# hv_Isolation.net
KiCad netlist of a schematic drawn in Altium Designer
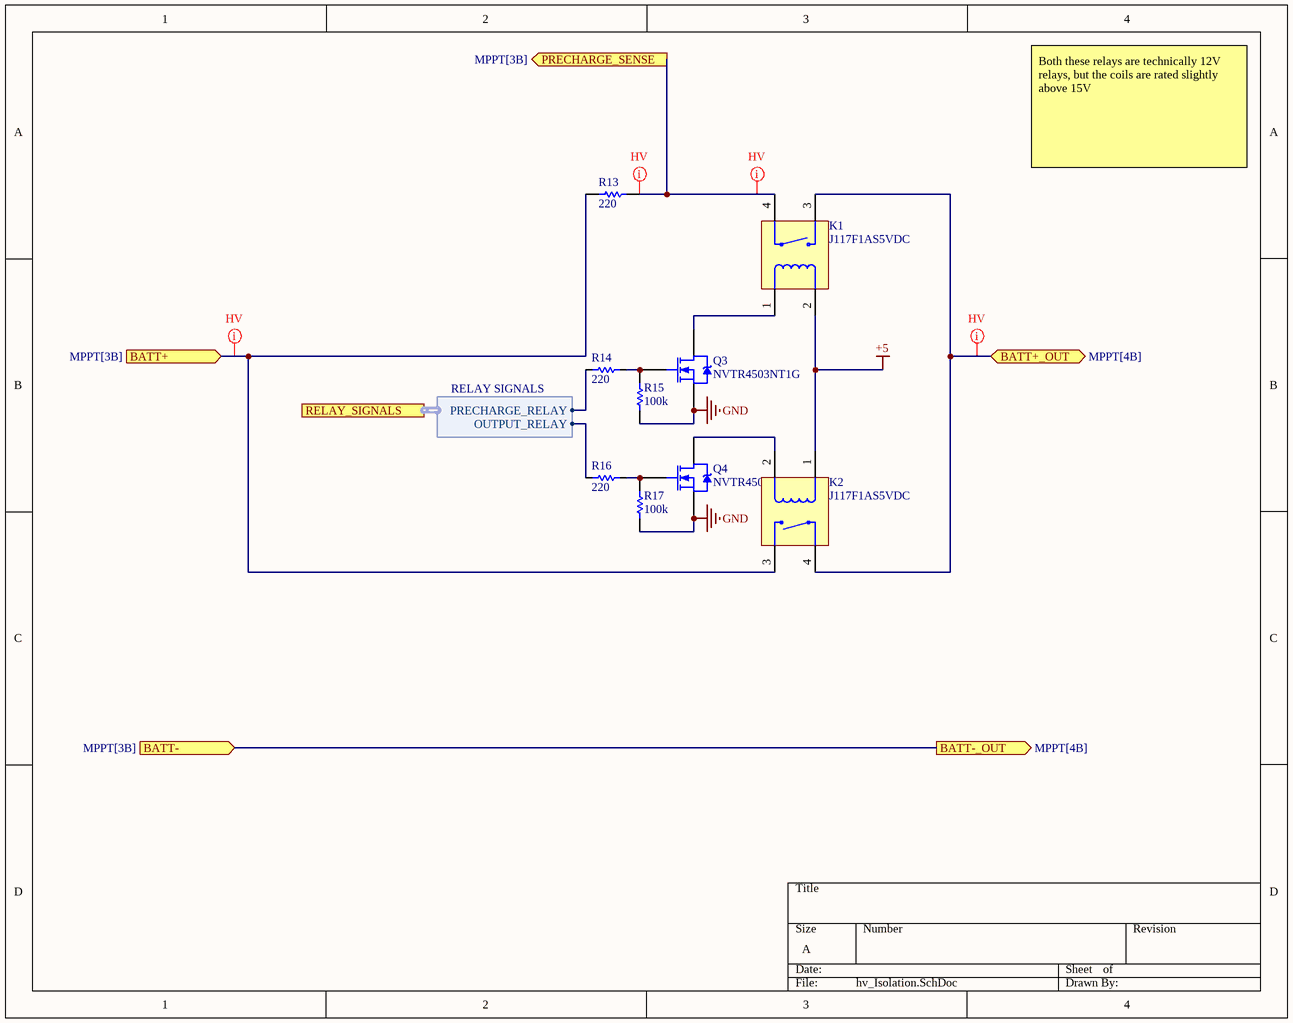
[diagram p0: hv_Isolation.SchDoc]

(export (version "E")
  (design (tool "Eeschema 10.0.6"))
  (components
    (comp (ref "K1")
      (value "J117F1AS5VDC")
      (footprint "J117F1AS5VDC-Footprint")
      (description "Relay Gen Purpose SPST 10A 5V")
      (libsource (lib "University of Minnesota - Solar Vehicle Project") (part "Symbol"))
    )
    (comp (ref "K2")
      (value "J117F1AS5VDC")
      (footprint "J117F1AS5VDC-Footprint")
      (description "Relay Gen Purpose SPST 10A 5V")
      (libsource (lib "") (part "Symbol_2"))
    )
    (comp (ref "Q3")
      (value "NVTR4503NT1G")
      (footprint "SOT-23_N")
      (libsource (lib "University of Minnesota - Solar Vehicle Project") (part "Q_MOSFET N-CH 30V 5A"))
    )
    (comp (ref "Q4")
      (value "NVTR4503NT1G")
      (footprint "SOT-23_N")
      (libsource (lib "University of Minnesota - Solar Vehicle Project") (part "Q_MOSFET N-CH 30V 5A"))
    )
    (comp (ref "R13")
      (value "220")
      (footprint "R_Res_Axial_SQP_THRU")
      (description "Fixed Resistor, Wire Wound, 10W, 220ohm, 750V, 5% +/-Tol, 300ppm/Cel, Through Hole Mount")
      (fields (field (name "TOLERANCE") "5%") (field (name "POWER") "10W"))
      (libsource (lib "University of Minnesota - Solar Vehicle Project") (part "RES-2"))
    )
    (comp (ref "R14")
      (value "220")
      (footprint "0603_RESISTOR")
      (description "RES 220 OHM 1/16W 1% 0603 SMD")
      (fields (field (name "POWER") "62.5mW") (field (name "TOLERANCE") "1%"))
      (libsource (lib "") (part "Symbol_1"))
    )
    (comp (ref "R15")
      (value "100k")
      (footprint "RESC1608X55X25ML10T15")
      (description "Chip Resistor, 100 KOhm, +/- 1%, 0.1 W, -55 to 155 degC, 0603 (1608 Metric)")
      (fields (field (name "POWER") "100mW") (field (name "TOLERANCE") "1%"))
      (libsource (lib "University of Minnesota - Solar Vehicle Project") (part "RES-2"))
    )
    (comp (ref "R16")
      (value "220")
      (footprint "0603_RESISTOR")
      (description "RES 220 OHM 1/16W 1% 0603 SMD")
      (fields (field (name "POWER") "62.5mW") (field (name "TOLERANCE") "1%"))
      (libsource (lib "") (part "Symbol_1"))
    )
    (comp (ref "R17")
      (value "100k")
      (footprint "RESC1608X55X25ML10T15")
      (description "Chip Resistor, 100 KOhm, +/- 1%, 0.1 W, -55 to 155 degC, 0603 (1608 Metric)")
      (fields (field (name "POWER") "100mW") (field (name "TOLERANCE") "1%"))
      (libsource (lib "University of Minnesota - Solar Vehicle Project") (part "RES-2"))
    )
  )
  (nets
    (net (code "3") (name "+5") (class "Default")
      (node (ref "K1") (pin "2") (pinfunction "CTRL-_2") (pintype "passive"))
      (node (ref "K2") (pin "1") (pinfunction "CTRL+_1") (pintype "passive"))
    )
    (net (code "4") (name "/BATT+") (class "Default")
      (node (ref "K2") (pin "3") (pinfunction "DC-_3") (pintype "passive"))
      (node (ref "R13") (pin "1") (pinfunction "1_1") (pintype "passive"))
    )
    (net (code "5") (name "/BATT+_OUT") (class "Default")
      (node (ref "K1") (pin "3") (pinfunction "DC-_3") (pintype "passive"))
      (node (ref "K2") (pin "4") (pinfunction "DC+_4") (pintype "passive"))
    )
    (net (code "7") (name "/OUTPUT_RELAY") (class "Default")
      (node (ref "R16") (pin "1") (pinfunction "1_1") (pintype "passive"))
    )
    (net (code "8") (name "/PRECHARGE_RELAY") (class "Default")
      (node (ref "R14") (pin "1") (pinfunction "1_1") (pintype "passive"))
    )
    (net (code "9") (name "/PRECHARGE_SENSE") (class "Default")
      (node (ref "K1") (pin "4") (pinfunction "DC+_4") (pintype "passive"))
      (node (ref "R13") (pin "2") (pinfunction "2_2") (pintype "passive"))
    )
    (net (code "11") (name "GND") (class "Default")
      (node (ref "Q3") (pin "2") (pinfunction "S_2") (pintype "passive"))
      (node (ref "Q4") (pin "2") (pinfunction "S_2") (pintype "passive"))
      (node (ref "R15") (pin "1") (pinfunction "1_1") (pintype "passive"))
      (node (ref "R17") (pin "1") (pinfunction "1_1") (pintype "passive"))
    )
    (net (code "12") (name "Net-(K1-CTRL+)") (class "Default")
      (node (ref "K1") (pin "1") (pinfunction "CTRL+_1") (pintype "passive"))
      (node (ref "Q3") (pin "3") (pinfunction "D_3") (pintype "passive"))
    )
    (net (code "13") (name "Net-(K2-CTRL-)") (class "Default")
      (node (ref "K2") (pin "2") (pinfunction "CTRL-_2") (pintype "passive"))
      (node (ref "Q4") (pin "3") (pinfunction "D_3") (pintype "passive"))
    )
    (net (code "14") (name "Net-(Q3-G)") (class "Default")
      (node (ref "Q3") (pin "1") (pinfunction "G_1") (pintype "passive"))
      (node (ref "R14") (pin "2") (pinfunction "2_2") (pintype "passive"))
      (node (ref "R15") (pin "2") (pinfunction "2_2") (pintype "passive"))
    )
    (net (code "15") (name "Net-(Q4-G)") (class "Default")
      (node (ref "Q4") (pin "1") (pinfunction "G_1") (pintype "passive"))
      (node (ref "R16") (pin "2") (pinfunction "2_2") (pintype "passive"))
      (node (ref "R17") (pin "2") (pinfunction "2_2") (pintype "passive"))
    )
  )
)
